# leg_group.net
KiCad netlist of a schematic drawn in Altium Designer
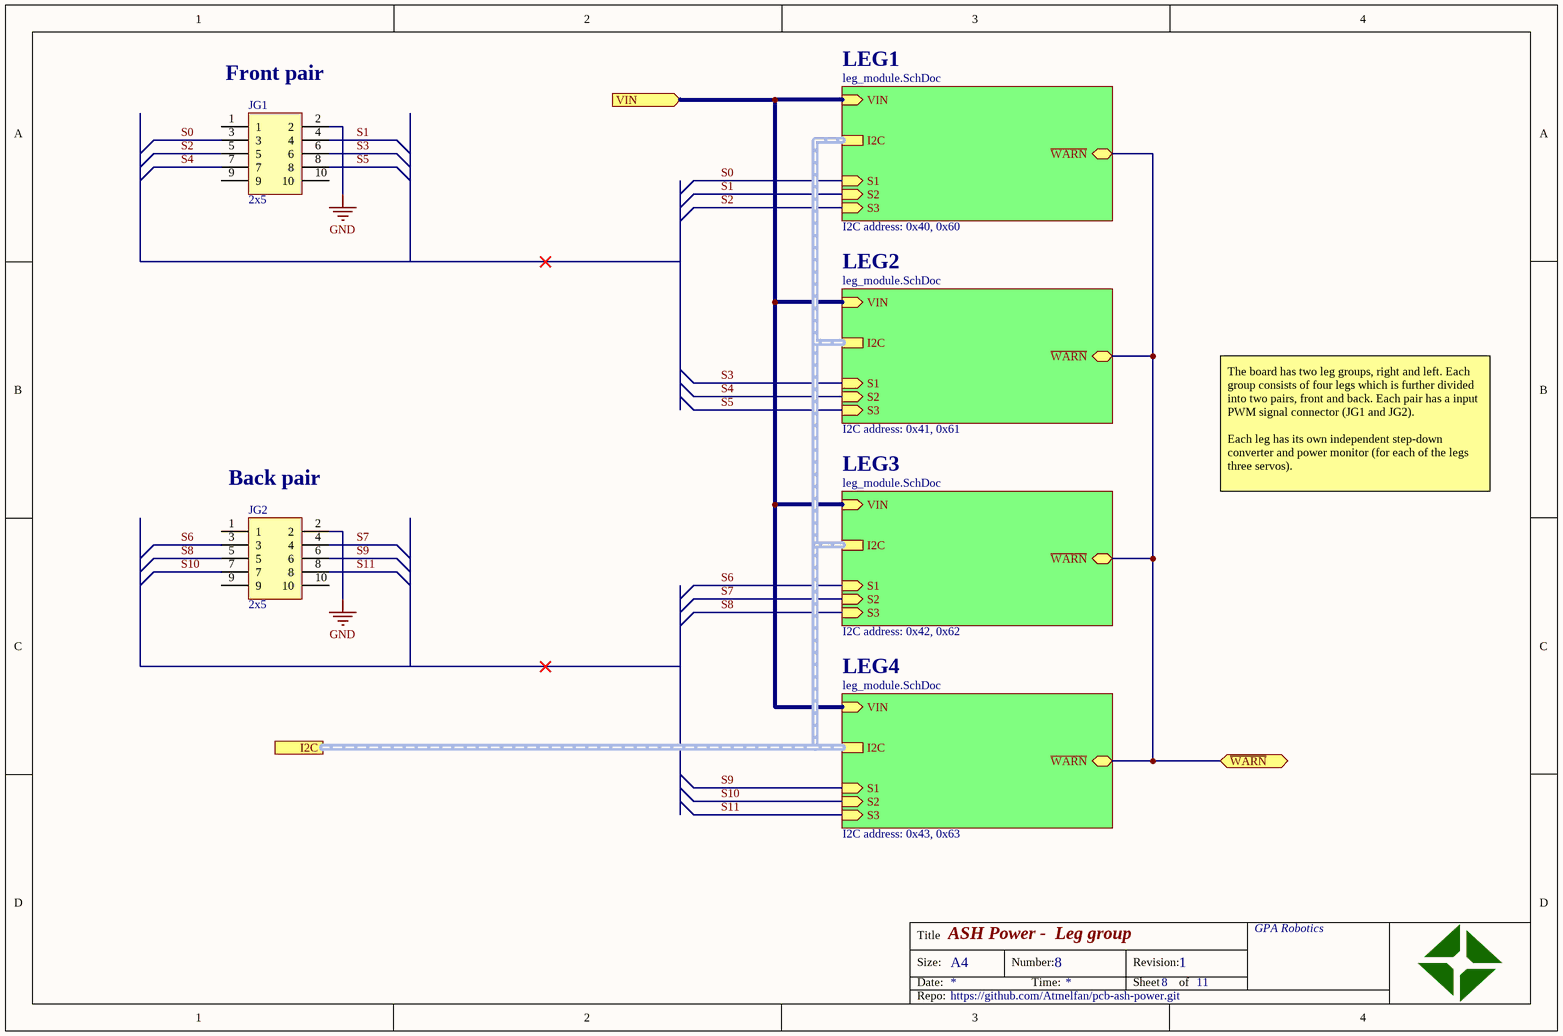
[diagram p0: leg_group.SchDoc]

(export (version "E")
  (design (tool "Eeschema 10.0.6"))
  (components
    (comp (ref "JG1")
      (value "2x5")
      (footprint "hdr_2x5_50mil")
      (description "2x5 Header")
      (libsource (lib "lib_connectors") (part "hdr_2x5"))
    )
    (comp (ref "JG2")
      (value "2x5")
      (footprint "hdr_2x5_50mil")
      (description "2x5 Header")
      (libsource (lib "lib_connectors") (part "hdr_2x5"))
    )
  )
  (nets
    (net (code "3") (name "/S0") (class "Default")
      (node (ref "JG1") (pin "3") (pinfunction "3_3") (pintype "passive"))
    )
    (net (code "4") (name "/S1") (class "Default")
      (node (ref "JG1") (pin "4") (pinfunction "4_4") (pintype "passive"))
    )
    (net (code "5") (name "/S2") (class "Default")
      (node (ref "JG1") (pin "5") (pinfunction "5_5") (pintype "passive"))
    )
    (net (code "6") (name "/S3") (class "Default")
      (node (ref "JG1") (pin "6") (pinfunction "6_6") (pintype "passive"))
    )
    (net (code "7") (name "/S4") (class "Default")
      (node (ref "JG1") (pin "7") (pinfunction "7_7") (pintype "passive"))
    )
    (net (code "8") (name "/S5") (class "Default")
      (node (ref "JG1") (pin "8") (pinfunction "8_8") (pintype "passive"))
    )
    (net (code "9") (name "/S6") (class "Default")
      (node (ref "JG2") (pin "3") (pinfunction "3_3") (pintype "passive"))
    )
    (net (code "10") (name "/S7") (class "Default")
      (node (ref "JG2") (pin "4") (pinfunction "4_4") (pintype "passive"))
    )
    (net (code "11") (name "/S8") (class "Default")
      (node (ref "JG2") (pin "5") (pinfunction "5_5") (pintype "passive"))
    )
    (net (code "12") (name "/S9") (class "Default")
      (node (ref "JG2") (pin "6") (pinfunction "6_6") (pintype "passive"))
    )
    (net (code "13") (name "/S10") (class "Default")
      (node (ref "JG2") (pin "7") (pinfunction "7_7") (pintype "passive"))
    )
    (net (code "14") (name "/S11") (class "Default")
      (node (ref "JG2") (pin "8") (pinfunction "8_8") (pintype "passive"))
    )
    (net (code "17") (name "GND") (class "Default")
      (node (ref "JG1") (pin "2") (pinfunction "2_2") (pintype "passive"))
      (node (ref "JG2") (pin "2") (pinfunction "2_2") (pintype "passive"))
    )
    (net (code "18") (name "unconnected-(JG1-Pad1)") (class "Default")
      (node (ref "JG1") (pin "1") (pinfunction "1_1") (pintype "passive"))
    )
    (net (code "19") (name "unconnected-(JG1-Pad9)") (class "Default")
      (node (ref "JG1") (pin "9") (pinfunction "9_9") (pintype "passive"))
    )
    (net (code "20") (name "unconnected-(JG1-Pad10)") (class "Default")
      (node (ref "JG1") (pin "10") (pinfunction "10_10") (pintype "passive"))
    )
    (net (code "21") (name "unconnected-(JG2-Pad1)") (class "Default")
      (node (ref "JG2") (pin "1") (pinfunction "1_1") (pintype "passive"))
    )
    (net (code "22") (name "unconnected-(JG2-Pad9)") (class "Default")
      (node (ref "JG2") (pin "9") (pinfunction "9_9") (pintype "passive"))
    )
    (net (code "23") (name "unconnected-(JG2-Pad10)") (class "Default")
      (node (ref "JG2") (pin "10") (pinfunction "10_10") (pintype "passive"))
    )
  )
)
